# USART.net
KiCad netlist of a schematic drawn in Altium Designer
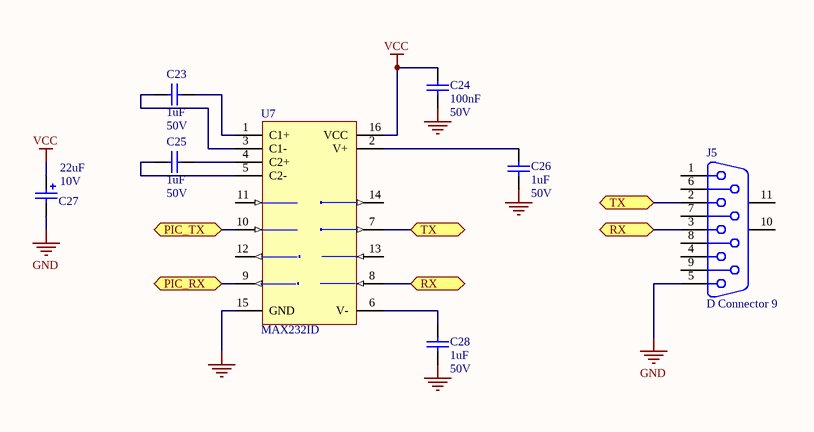
[diagram p0: USART.SchDoc]

(export (version "E")
  (design (tool "Eeschema 10.0.6"))
  (components
    (comp (ref "C23")
      (value "1uF")
      (footprint "3-0603_L")
      (description "Capacitor")
      (fields
        (field (name "VOLTAGE") "50V")
        (field (name "Comment") "Cap")
        (field (name "PUBLISHER") "Altium Limited")
      )
      (libsource (lib "Erdem_05112012") (part "Cap"))
    )
    (comp (ref "C24")
      (value "100nF")
      (footprint "3-0603_L")
      (description "Capacitor")
      (fields
        (field (name "VOLTAGE") "50V")
        (field (name "Comment") "Cap")
        (field (name "PUBLISHER") "Altium Limited")
      )
      (libsource (lib "Erdem_05112012") (part "Cap"))
    )
    (comp (ref "C25")
      (value "1uF")
      (footprint "3-0603_L")
      (description "Capacitor")
      (fields
        (field (name "VOLTAGE") "50V")
        (field (name "Comment") "Cap")
        (field (name "PUBLISHER") "Altium Limited")
      )
      (libsource (lib "Erdem_05112012") (part "Cap"))
    )
    (comp (ref "C26")
      (value "1uF")
      (footprint "3-0603_L")
      (description "Capacitor")
      (fields
        (field (name "VOLTAGE") "50V")
        (field (name "Comment") "Cap")
        (field (name "PUBLISHER") "Altium Limited")
      )
      (libsource (lib "Erdem_05112012") (part "Cap"))
    )
    (comp (ref "C27")
      (value "22uF")
      (footprint "3528")
      (fields
        (field (name "VOLTAGE") "10V")
        (field (name "Comment") "CAP-Tantal")
        (field (name "PUBLISHER") "Altium Limited")
      )
      (libsource (lib "Erdem_05112012") (part "CAP-Tantal"))
    )
    (comp (ref "C28")
      (value "1uF")
      (footprint "3-0603_L")
      (description "Capacitor")
      (fields
        (field (name "VOLTAGE") "50V")
        (field (name "Comment") "Cap")
        (field (name "PUBLISHER") "Altium Limited")
      )
      (libsource (lib "Erdem_05112012") (part "Cap"))
    )
    (comp (ref "J5")
      (value "D Connector 9")
      (footprint "DSUB1.385-2H9")
      (description "Receptacle Assembly, 9 Position, Right Angle")
      (fields (field (name "PUBLISHER") "Altium Limited"))
      (libsource (lib "Miscellaneous Connectors") (part "D Connector 9"))
    )
    (comp (ref "U7")
      (value "MAX232ID")
      (footprint "SOIC16 - big")
      (description "5V, Low-Power, up to 1Mbps, True RS-232 Transceiver Using Four 0.1µF External Capacitor")
      (fields (field (name "PUBLISHER") "Altium Limited"))
      (libsource (lib "Erdem_05112012") (part "MAX232ID"))
    )
  )
  (nets
    (net (code "1") (name "/PIC_RX") (class "Default")
      (node (ref "U7") (pin "9") (pinfunction "R2OUT_9") (pintype "output"))
    )
    (net (code "2") (name "/PIC_TX") (class "Default")
      (node (ref "U7") (pin "10") (pinfunction "T2IN_10") (pintype "input"))
    )
    (net (code "3") (name "/RX") (class "Default")
      (node (ref "J5") (pin "3") (pinfunction "3_3") (pintype "passive"))
      (node (ref "U7") (pin "8") (pinfunction "R2IN_8") (pintype "input"))
    )
    (net (code "4") (name "/TX") (class "Default")
      (node (ref "J5") (pin "2") (pinfunction "2_2") (pintype "passive"))
      (node (ref "U7") (pin "7") (pinfunction "T2OUT_7") (pintype "output"))
    )
    (net (code "5") (name "GND") (class "Default")
      (node (ref "C24") (pin "1") (pinfunction "1_1") (pintype "passive"))
      (node (ref "C26") (pin "2") (pinfunction "2_2") (pintype "passive"))
      (node (ref "C27") (pin "2") (pinfunction "2_2") (pintype "passive"))
      (node (ref "C28") (pin "2") (pinfunction "2_2") (pintype "passive"))
      (node (ref "J5") (pin "5") (pinfunction "5_5") (pintype "passive"))
      (node (ref "U7") (pin "15") (pinfunction "GND_15") (pintype "power_in"))
    )
    (net (code "6") (name "Net-(U7-C1+)") (class "Default")
      (node (ref "C23") (pin "1") (pinfunction "1_1") (pintype "passive"))
      (node (ref "U7") (pin "1") (pinfunction "C1+_1") (pintype "passive"))
    )
    (net (code "7") (name "Net-(U7-C1-)") (class "Default")
      (node (ref "C23") (pin "2") (pinfunction "2_2") (pintype "passive"))
      (node (ref "U7") (pin "3") (pinfunction "C1-_3") (pintype "passive"))
    )
    (net (code "8") (name "Net-(U7-C2+)") (class "Default")
      (node (ref "C25") (pin "1") (pinfunction "1_1") (pintype "passive"))
      (node (ref "U7") (pin "4") (pinfunction "C2+_4") (pintype "passive"))
    )
    (net (code "9") (name "Net-(U7-C2-)") (class "Default")
      (node (ref "C25") (pin "2") (pinfunction "2_2") (pintype "passive"))
      (node (ref "U7") (pin "5") (pinfunction "C2-_5") (pintype "passive"))
    )
    (net (code "10") (name "Net-(U7-V+)") (class "Default")
      (node (ref "C26") (pin "1") (pinfunction "1_1") (pintype "passive"))
      (node (ref "U7") (pin "2") (pinfunction "V+_2") (pintype "power_in"))
    )
    (net (code "11") (name "Net-(U7-V-)") (class "Default")
      (node (ref "C28") (pin "1") (pinfunction "1_1") (pintype "passive"))
      (node (ref "U7") (pin "6") (pinfunction "V-_6") (pintype "power_in"))
    )
    (net (code "12") (name "VCC") (class "Default")
      (node (ref "C24") (pin "2") (pinfunction "2_2") (pintype "passive"))
      (node (ref "C27") (pin "1") (pinfunction "1_1") (pintype "passive"))
      (node (ref "U7") (pin "16") (pinfunction "VCC_16") (pintype "power_in"))
    )
    (net (code "13") (name "unconnected-(J5-MH1-Pad10)") (class "Default")
      (node (ref "J5") (pin "10") (pinfunction "MH1_10") (pintype "passive"))
    )
    (net (code "14") (name "unconnected-(J5-MH2-Pad11)") (class "Default")
      (node (ref "J5") (pin "11") (pinfunction "MH2_11") (pintype "passive"))
    )
    (net (code "15") (name "unconnected-(J5-Pad1)") (class "Default")
      (node (ref "J5") (pin "1") (pinfunction "1_1") (pintype "passive"))
    )
    (net (code "16") (name "unconnected-(J5-Pad4)") (class "Default")
      (node (ref "J5") (pin "4") (pinfunction "4_4") (pintype "passive"))
    )
    (net (code "17") (name "unconnected-(J5-Pad6)") (class "Default")
      (node (ref "J5") (pin "6") (pinfunction "6_6") (pintype "passive"))
    )
    (net (code "18") (name "unconnected-(J5-Pad7)") (class "Default")
      (node (ref "J5") (pin "7") (pinfunction "7_7") (pintype "passive"))
    )
    (net (code "19") (name "unconnected-(J5-Pad8)") (class "Default")
      (node (ref "J5") (pin "8") (pinfunction "8_8") (pintype "passive"))
    )
    (net (code "20") (name "unconnected-(J5-Pad9)") (class "Default")
      (node (ref "J5") (pin "9") (pinfunction "9_9") (pintype "passive"))
    )
    (net (code "21") (name "unconnected-(U7-R1IN-Pad13)") (class "Default")
      (node (ref "U7") (pin "13") (pinfunction "R1IN_13") (pintype "input"))
    )
    (net (code "22") (name "unconnected-(U7-R1OUT-Pad12)") (class "Default")
      (node (ref "U7") (pin "12") (pinfunction "R1OUT_12") (pintype "output"))
    )
    (net (code "23") (name "unconnected-(U7-T1IN-Pad11)") (class "Default")
      (node (ref "U7") (pin "11") (pinfunction "T1IN_11") (pintype "input"))
    )
    (net (code "24") (name "unconnected-(U7-T1OUT-Pad14)") (class "Default")
      (node (ref "U7") (pin "14") (pinfunction "T1OUT_14") (pintype "output"))
    )
  )
)
